# Adafruit_Stemma_QT_5_Port_Hub.net
KiCad netlist of a schematic drawn in EAGLE
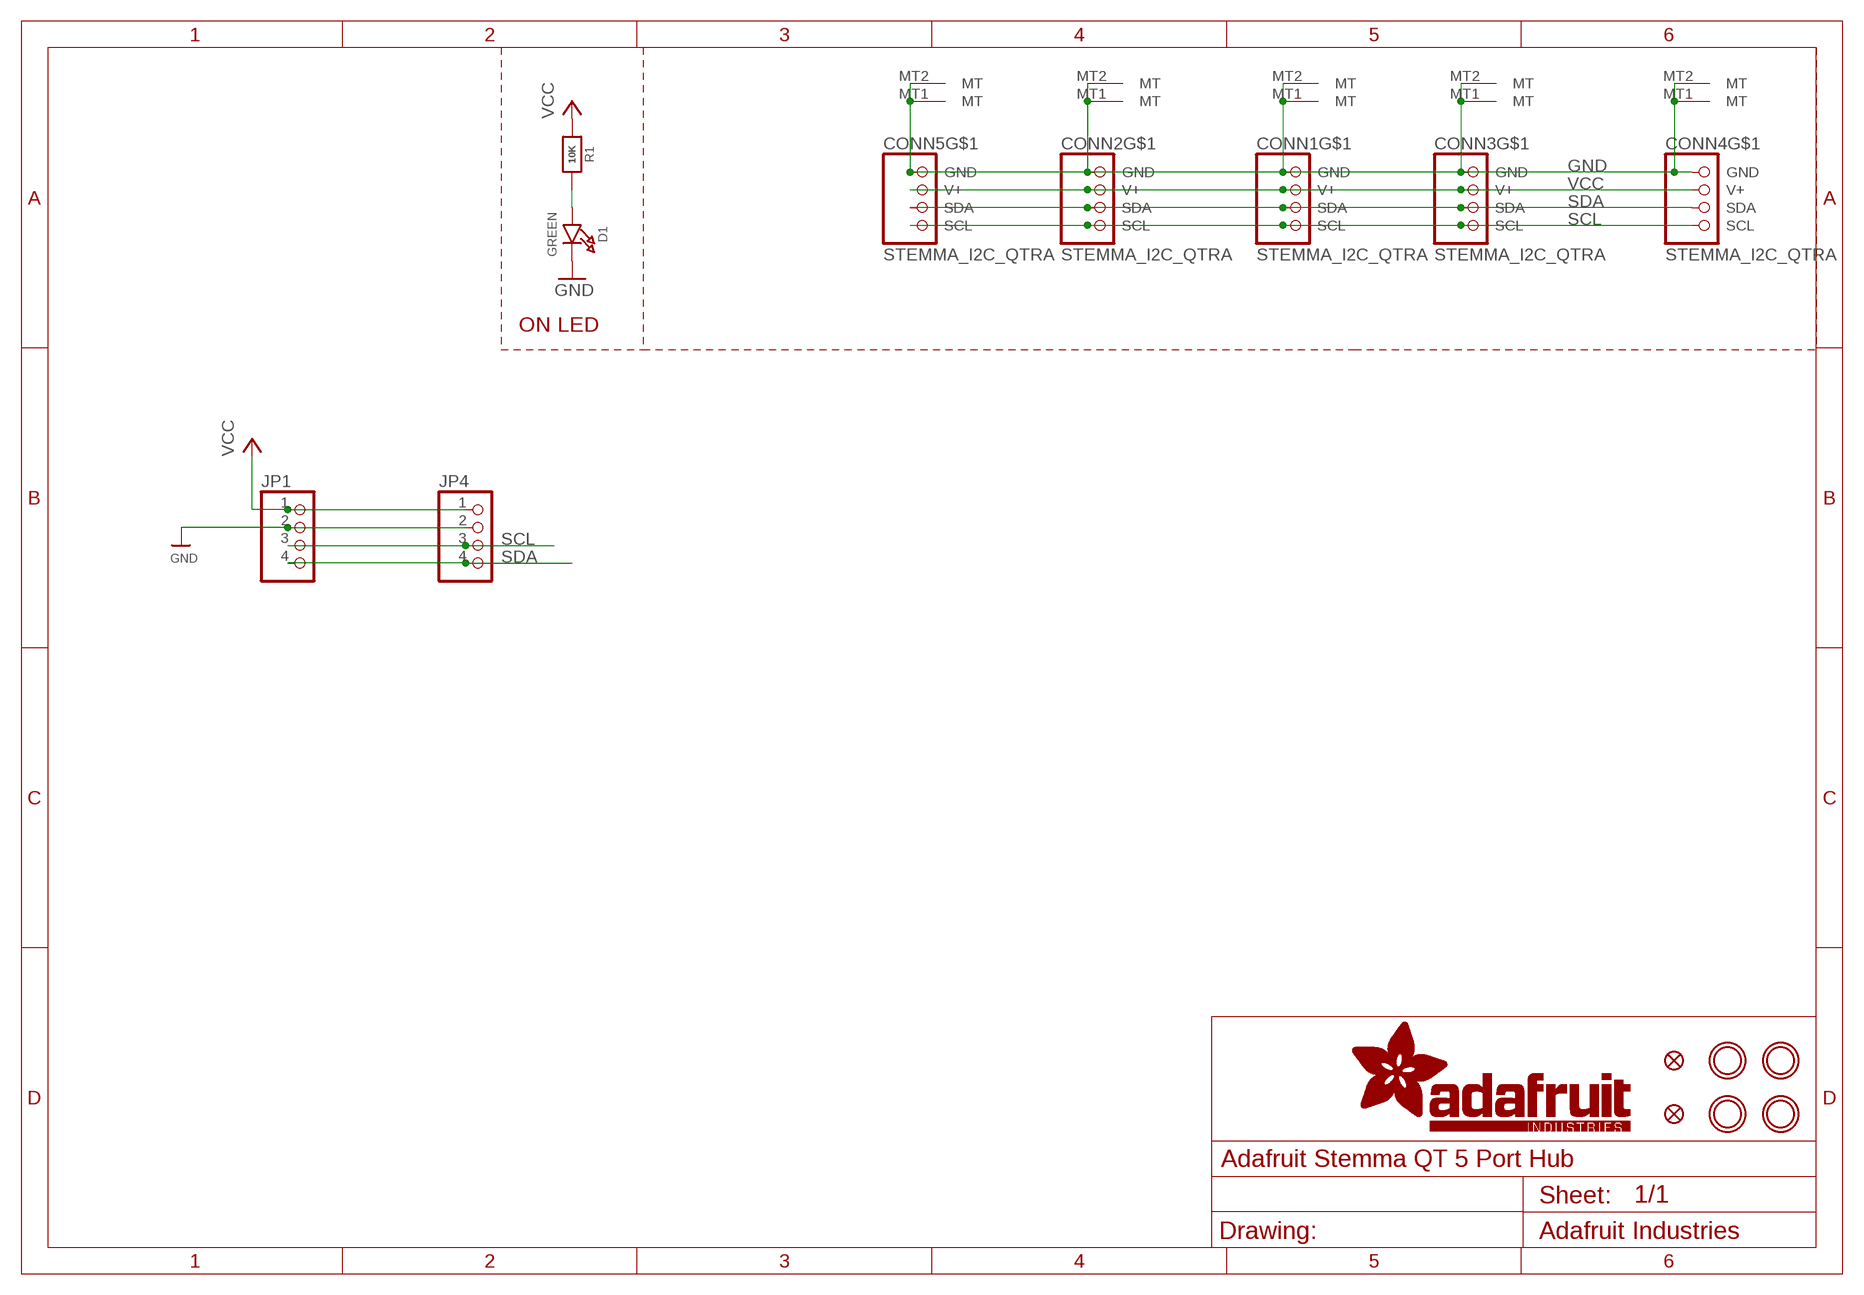
[diagram p0: schematic, sheet 1]

(export (version "E")
  (design (tool "Eeschema 10.0.6"))
  (components
    (comp (ref "CONN1")
      (value "STEMMA_I2C_QTRA")
      (footprint "eagle-import:JST_SH4_RA")
      (libsource (lib "eagle-import") (part "STEMMA_I2C_QTRA"))
    )
    (comp (ref "CONN2")
      (value "STEMMA_I2C_QTRA")
      (footprint "eagle-import:JST_SH4_RA")
      (libsource (lib "eagle-import") (part "STEMMA_I2C_QTRA"))
    )
    (comp (ref "CONN3")
      (value "STEMMA_I2C_QTRA")
      (footprint "eagle-import:JST_SH4_RA")
      (libsource (lib "eagle-import") (part "STEMMA_I2C_QTRA"))
    )
    (comp (ref "CONN4")
      (value "STEMMA_I2C_QTRA")
      (footprint "eagle-import:JST_SH4_RA")
      (libsource (lib "eagle-import") (part "STEMMA_I2C_QTRA"))
    )
    (comp (ref "CONN5")
      (value "STEMMA_I2C_QTRA")
      (footprint "eagle-import:JST_SH4_RA")
      (libsource (lib "eagle-import") (part "STEMMA_I2C_QTRA"))
    )
    (comp (ref "D1")
      (value "GREEN")
      (footprint "eagle-import:CHIPLED_0603_NOOUTLINE")
      (libsource (lib "eagle-import") (part "LED0603_NOOUTLINE"))
    )
    (comp (ref "FID3")
      (value "FIDUCIAL_1MM")
      (footprint "eagle-import:FIDUCIAL_1MM")
      (libsource (lib "eagle-import") (part "FIDUCIAL_1MM"))
    )
    (comp (ref "FID4")
      (value "FIDUCIAL_1MM")
      (footprint "eagle-import:FIDUCIAL_1MM")
      (libsource (lib "eagle-import") (part "FIDUCIAL_1MM"))
    )
    (comp (ref "JP1")
      (value "HEADER-1X476MIL")
      (footprint "eagle-import:1X04_ROUND_76")
      (libsource (lib "eagle-import") (part "HEADER-1X476MIL"))
    )
    (comp (ref "JP4")
      (value "HEADER-1X476MIL")
      (footprint "eagle-import:1X04_ROUND_76")
      (libsource (lib "eagle-import") (part "HEADER-1X476MIL"))
    )
    (comp (ref "R1")
      (value "10K")
      (footprint "eagle-import:0603-NO")
      (libsource (lib "eagle-import") (part "RESISTOR_0603_NOOUT"))
    )
    (comp (ref "U$1")
      (value "MOUNTINGHOLE2.5")
      (footprint "eagle-import:MOUNTINGHOLE_2.5_PLATED")
      (libsource (lib "eagle-import") (part "MOUNTINGHOLE2.5"))
    )
    (comp (ref "U$17")
      (value "MOUNTINGHOLE2.5")
      (footprint "eagle-import:MOUNTINGHOLE_2.5_PLATED")
      (libsource (lib "eagle-import") (part "MOUNTINGHOLE2.5"))
    )
    (comp (ref "U$19")
      (value "MOUNTINGHOLE2.5")
      (footprint "eagle-import:MOUNTINGHOLE_2.5_PLATED")
      (libsource (lib "eagle-import") (part "MOUNTINGHOLE2.5"))
    )
    (comp (ref "U$21")
      (value "MOUNTINGHOLE2.5")
      (footprint "eagle-import:MOUNTINGHOLE_2.5_PLATED")
      (libsource (lib "eagle-import") (part "MOUNTINGHOLE2.5"))
    )
  )
  (nets
    (net (code "1") (name "/SCL") (class "Default")
      (node (ref "CONN1") (pin "4") (pinfunction "SCL_4") (pintype "passive"))
      (node (ref "CONN2") (pin "4") (pinfunction "SCL_4") (pintype "passive"))
      (node (ref "CONN3") (pin "4") (pinfunction "SCL_4") (pintype "passive"))
      (node (ref "CONN4") (pin "4") (pinfunction "SCL_4") (pintype "passive"))
      (node (ref "CONN5") (pin "4") (pinfunction "SCL_4") (pintype "passive"))
      (node (ref "JP1") (pin "3") (pinfunction "3_3") (pintype "passive"))
      (node (ref "JP4") (pin "3") (pinfunction "3_3") (pintype "passive"))
    )
    (net (code "2") (name "/SDA") (class "Default")
      (node (ref "CONN1") (pin "3") (pinfunction "SDA_3") (pintype "passive"))
      (node (ref "CONN2") (pin "3") (pinfunction "SDA_3") (pintype "passive"))
      (node (ref "CONN3") (pin "3") (pinfunction "SDA_3") (pintype "passive"))
      (node (ref "CONN4") (pin "3") (pinfunction "SDA_3") (pintype "passive"))
      (node (ref "CONN5") (pin "3") (pinfunction "SDA_3") (pintype "passive"))
      (node (ref "JP1") (pin "4") (pinfunction "4_4") (pintype "passive"))
      (node (ref "JP4") (pin "4") (pinfunction "4_4") (pintype "passive"))
    )
    (net (code "3") (name "GND") (class "Default")
      (node (ref "CONN1") (pin "1") (pinfunction "GND_1") (pintype "passive"))
      (node (ref "CONN1") (pin "MT1") (pinfunction "MT_MT1") (pintype "bidirectional"))
      (node (ref "CONN1") (pin "MT2") (pinfunction "MT_MT2") (pintype "bidirectional"))
      (node (ref "CONN2") (pin "1") (pinfunction "GND_1") (pintype "passive"))
      (node (ref "CONN2") (pin "MT1") (pinfunction "MT_MT1") (pintype "bidirectional"))
      (node (ref "CONN2") (pin "MT2") (pinfunction "MT_MT2") (pintype "bidirectional"))
      (node (ref "CONN3") (pin "1") (pinfunction "GND_1") (pintype "passive"))
      (node (ref "CONN3") (pin "MT1") (pinfunction "MT_MT1") (pintype "bidirectional"))
      (node (ref "CONN3") (pin "MT2") (pinfunction "MT_MT2") (pintype "bidirectional"))
      (node (ref "CONN4") (pin "1") (pinfunction "GND_1") (pintype "passive"))
      (node (ref "CONN4") (pin "MT1") (pinfunction "MT_MT1") (pintype "bidirectional"))
      (node (ref "CONN4") (pin "MT2") (pinfunction "MT_MT2") (pintype "bidirectional"))
      (node (ref "CONN5") (pin "1") (pinfunction "GND_1") (pintype "passive"))
      (node (ref "CONN5") (pin "MT1") (pinfunction "MT_MT1") (pintype "bidirectional"))
      (node (ref "CONN5") (pin "MT2") (pinfunction "MT_MT2") (pintype "bidirectional"))
      (node (ref "D1") (pin "C") (pinfunction "C_C") (pintype "passive"))
      (node (ref "JP1") (pin "2") (pinfunction "2_2") (pintype "passive"))
      (node (ref "JP4") (pin "2") (pinfunction "2_2") (pintype "passive"))
    )
    (net (code "4") (name "Net-(D1-PadA)") (class "Default")
      (node (ref "D1") (pin "A") (pinfunction "A_A") (pintype "passive"))
      (node (ref "R1") (pin "2") (pinfunction "2_2") (pintype "passive"))
    )
    (net (code "5") (name "VCC") (class "Default")
      (node (ref "CONN1") (pin "2") (pinfunction "V+_2") (pintype "passive"))
      (node (ref "CONN2") (pin "2") (pinfunction "V+_2") (pintype "passive"))
      (node (ref "CONN3") (pin "2") (pinfunction "V+_2") (pintype "passive"))
      (node (ref "CONN4") (pin "2") (pinfunction "V+_2") (pintype "passive"))
      (node (ref "CONN5") (pin "2") (pinfunction "V+_2") (pintype "passive"))
      (node (ref "JP1") (pin "1") (pinfunction "1_1") (pintype "passive"))
      (node (ref "JP4") (pin "1") (pinfunction "1_1") (pintype "passive"))
      (node (ref "R1") (pin "1") (pinfunction "1_1") (pintype "passive"))
    )
  )
)
